# BSPD.net
KiCad netlist of a schematic drawn in Altium Designer
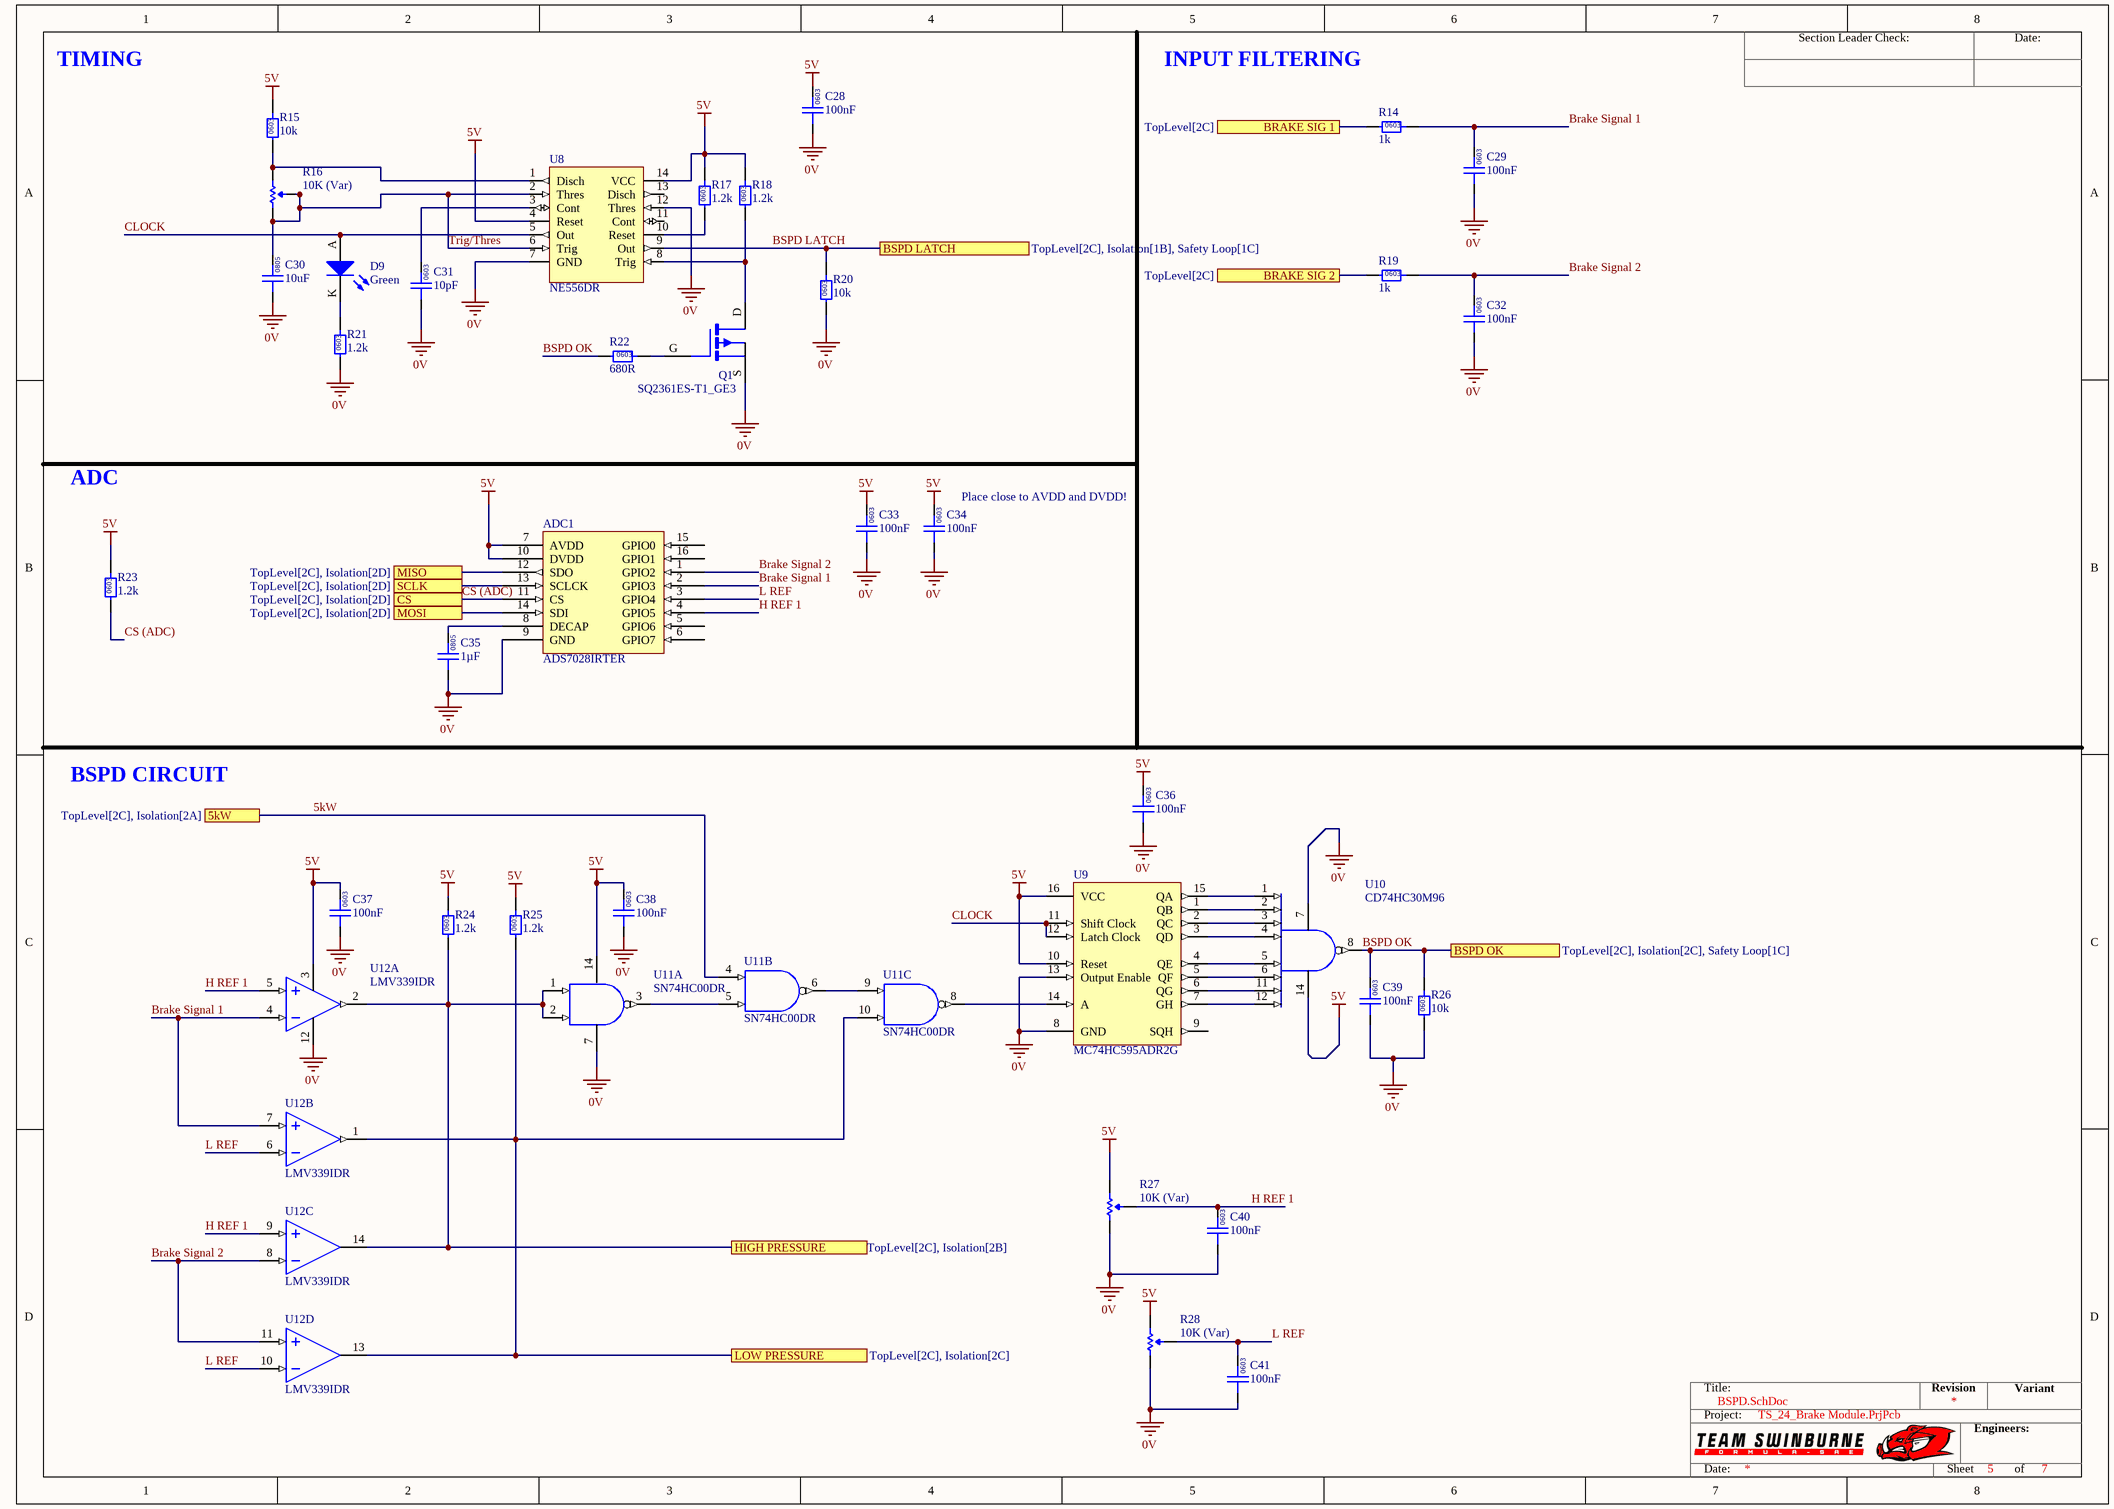
[diagram p0: BSPD.SchDoc]

(export (version "E")
  (design (tool "Eeschema 10.0.6"))
  (components
    (comp (ref "ADC1")
      (value "ADS7028IRTER")
      (footprint "WFQN-16")
      (description "IC ADC 12BIT SAR 16WQFN")
      (fields (field (name "MANUFACTURER") "Texas Instruments"))
      (libsource (lib "ts_standard_library") (part "ADS7028IRTER"))
    )
    (comp (ref "C28")
      (value "100nF")
      (footprint "0603")
      (fields
        (field (name "PART NUMBER") "GCM188L81H104KA57D")
        (field (name "MANUFACTURER") "muRata")
        (field (name "TOLERANCE") "±10%")
      )
      (libsource (lib "ts_standard_library") (part "Capacitor 0603"))
    )
    (comp (ref "C29")
      (value "100nF")
      (footprint "0603")
      (fields
        (field (name "PART NUMBER") "GCM188L81H104KA57D")
        (field (name "MANUFACTURER") "muRata")
        (field (name "TOLERANCE") "±10%")
      )
      (libsource (lib "ts_standard_library") (part "Capacitor 0603"))
    )
    (comp (ref "C30")
      (value "10uF")
      (footprint "0805")
      (fields
        (field (name "PART NUMBER") "GRM21BR6YA106KE43L")
        (field (name "MANUFACTURER") "muRata")
        (field (name "TOLERANCE") "10%")
      )
      (libsource (lib "ts_standard_library") (part "Capacitor 0805"))
    )
    (comp (ref "C31")
      (value "10pF")
      (footprint "0603")
      (fields
        (field (name "PART NUMBER") "GRM1885C1H100JA01D")
        (field (name "MANUFACTURER") "Murata Electronics")
        (field (name "TOLERANCE") "±5%")
      )
      (libsource (lib "ts_standard_library") (part "Capacitor 0603"))
    )
    (comp (ref "C32")
      (value "100nF")
      (footprint "0603")
      (fields
        (field (name "PART NUMBER") "GCM188L81H104KA57D")
        (field (name "MANUFACTURER") "muRata")
        (field (name "TOLERANCE") "±10%")
      )
      (libsource (lib "ts_standard_library") (part "Capacitor 0603"))
    )
    (comp (ref "C33")
      (value "100nF")
      (footprint "0603")
      (fields
        (field (name "PART NUMBER") "GCM188L81H104KA57D")
        (field (name "MANUFACTURER") "muRata")
        (field (name "TOLERANCE") "±10%")
      )
      (libsource (lib "ts_standard_library") (part "Capacitor 0603"))
    )
    (comp (ref "C34")
      (value "100nF")
      (footprint "0603")
      (fields
        (field (name "PART NUMBER") "GCM188L81H104KA57D")
        (field (name "MANUFACTURER") "muRata")
        (field (name "TOLERANCE") "±10%")
      )
      (libsource (lib "ts_standard_library") (part "Capacitor 0603"))
    )
    (comp (ref "C35")
      (value "1µF")
      (footprint "0805")
      (fields
        (field (name "PART NUMBER") "GCM21BR71H105KA03L")
        (field (name "MANUFACTURER") "muRata")
        (field (name "TOLERANCE") "±10%")
      )
      (libsource (lib "ts_standard_library") (part "Capacitor 0805"))
    )
    (comp (ref "C36")
      (value "100nF")
      (footprint "0603")
      (fields
        (field (name "PART NUMBER") "GCM188L81H104KA57D")
        (field (name "MANUFACTURER") "muRata")
        (field (name "TOLERANCE") "±10%")
      )
      (libsource (lib "ts_standard_library") (part "Capacitor 0603"))
    )
    (comp (ref "C37")
      (value "100nF")
      (footprint "0603")
      (fields
        (field (name "PART NUMBER") "GCM188L81H104KA57D")
        (field (name "MANUFACTURER") "muRata")
        (field (name "TOLERANCE") "±10%")
      )
      (libsource (lib "ts_standard_library") (part "Capacitor 0603"))
    )
    (comp (ref "C38")
      (value "100nF")
      (footprint "0603")
      (fields
        (field (name "PART NUMBER") "GCM188L81H104KA57D")
        (field (name "MANUFACTURER") "muRata")
        (field (name "TOLERANCE") "±10%")
      )
      (libsource (lib "ts_standard_library") (part "Capacitor 0603"))
    )
    (comp (ref "C39")
      (value "100nF")
      (footprint "0603")
      (fields
        (field (name "PART NUMBER") "GCM188L81H104KA57D")
        (field (name "MANUFACTURER") "muRata")
        (field (name "TOLERANCE") "±10%")
      )
      (libsource (lib "ts_standard_library") (part "Capacitor 0603"))
    )
    (comp (ref "C40")
      (value "100nF")
      (footprint "0603")
      (fields
        (field (name "PART NUMBER") "GCM188L81H104KA57D")
        (field (name "MANUFACTURER") "muRata")
        (field (name "TOLERANCE") "±10%")
      )
      (libsource (lib "ts_standard_library") (part "Capacitor 0603"))
    )
    (comp (ref "C41")
      (value "100nF")
      (footprint "0603")
      (fields
        (field (name "PART NUMBER") "GCM188L81H104KA57D")
        (field (name "MANUFACTURER") "muRata")
        (field (name "TOLERANCE") "±10%")
      )
      (libsource (lib "ts_standard_library") (part "Capacitor 0603"))
    )
    (comp (ref "D9")
      (value "Green")
      (footprint "0805 LED")
      (description "Green LED Indication - Discrete 1.75V 0805 (2012 Metric)")
      (fields (field (name "PART NUMBER") "SML-210FTT86") (field (name "MANUFACTURER") "ROHM Semiconductor"))
      (libsource (lib "ts_standard_library") (part "LED"))
    )
    (comp (ref "Q1")
      (value "SQ2361ES-T1_GE3")
      (footprint "VSHY SOT-23-3")
      (description "MOSFET P-CH 60V 2.8A SSOT23")
      (fields
        (field (name "MANUFACTURER") "Vishay Siliconix")
        (field (name "DIGIKEY PART NUMBER") "SQ2361ES-T1_GE3CT-ND")
        (field (name "PUBLISHER") "Altium Limited")
      )
      (libsource (lib "ts_standard_library") (part "MOSFET-P"))
    )
    (comp (ref "R14")
      (value "1k")
      (footprint "0603")
      (fields
        (field (name "PART NUMBER") "RC0603FR-071KL")
        (field (name "MANUFACTURER") "YAGEO")
        (field (name "TOLERANCE") "0.01")
      )
      (libsource (lib "ts_standard_library") (part "Resistor 0603"))
    )
    (comp (ref "R15")
      (value "10k")
      (footprint "0603")
      (fields
        (field (name "PART NUMBER") "RC0603FR-0710KL")
        (field (name "MANUFACTURER") "YAGEO")
        (field (name "TOLERANCE") "0.01")
      )
      (libsource (lib "ts_standard_library") (part "Resistor 0603"))
    )
    (comp (ref "R16")
      (value "10K (Var)")
      (footprint "B 3296")
      (fields
        (field (name "PART NUMBER") "3296W-1-103LF")
        (field (name "MANUFACTURER") "Bournes Inc")
        (field (name "TOLERANCE") "0.1")
      )
      (libsource (lib "ts_standard_library") (part "Resistor (Potentiometer)"))
    )
    (comp (ref "R17")
      (value "1.2k")
      (footprint "0603")
      (fields
        (field (name "PART NUMBER") "RC0603JR-071K2L")
        (field (name "MANUFACTURER") "YAGEO")
        (field (name "TOLERANCE") "0.01")
      )
      (libsource (lib "ts_standard_library") (part "Resistor 0603"))
    )
    (comp (ref "R18")
      (value "1.2k")
      (footprint "0603")
      (fields
        (field (name "PART NUMBER") "RC0603JR-071K2L")
        (field (name "MANUFACTURER") "YAGEO")
        (field (name "TOLERANCE") "0.01")
      )
      (libsource (lib "ts_standard_library") (part "Resistor 0603"))
    )
    (comp (ref "R19")
      (value "1k")
      (footprint "0603")
      (fields
        (field (name "PART NUMBER") "RC0603FR-071KL")
        (field (name "MANUFACTURER") "YAGEO")
        (field (name "TOLERANCE") "0.01")
      )
      (libsource (lib "ts_standard_library") (part "Resistor 0603"))
    )
    (comp (ref "R20")
      (value "10k")
      (footprint "0603")
      (fields
        (field (name "PART NUMBER") "RC0603FR-0710KL")
        (field (name "MANUFACTURER") "YAGEO")
        (field (name "TOLERANCE") "0.01")
      )
      (libsource (lib "ts_standard_library") (part "Resistor 0603"))
    )
    (comp (ref "R21")
      (value "1.2k")
      (footprint "0603")
      (fields
        (field (name "PART NUMBER") "RC0603JR-071K2L")
        (field (name "MANUFACTURER") "YAGEO")
        (field (name "TOLERANCE") "0.01")
      )
      (libsource (lib "ts_standard_library") (part "Resistor 0603"))
    )
    (comp (ref "R22")
      (value "680R")
      (footprint "0603")
      (fields
        (field (name "PART NUMBER") "RC0603JR-13680RL")
        (field (name "MANUFACTURER") "YAGEO")
        (field (name "TOLERANCE") "0.01")
      )
      (libsource (lib "ts_standard_library") (part "Resistor 0603"))
    )
    (comp (ref "R23")
      (value "1.2k")
      (footprint "0603")
      (fields
        (field (name "PART NUMBER") "RC0603JR-071K2L")
        (field (name "MANUFACTURER") "YAGEO")
        (field (name "TOLERANCE") "0.01")
      )
      (libsource (lib "ts_standard_library") (part "Resistor 0603"))
    )
    (comp (ref "R24")
      (value "1.2k")
      (footprint "0603")
      (fields
        (field (name "PART NUMBER") "RC0603JR-071K2L")
        (field (name "MANUFACTURER") "YAGEO")
        (field (name "TOLERANCE") "0.01")
      )
      (libsource (lib "ts_standard_library") (part "Resistor 0603"))
    )
    (comp (ref "R25")
      (value "1.2k")
      (footprint "0603")
      (fields
        (field (name "PART NUMBER") "RC0603JR-071K2L")
        (field (name "MANUFACTURER") "YAGEO")
        (field (name "TOLERANCE") "0.01")
      )
      (libsource (lib "ts_standard_library") (part "Resistor 0603"))
    )
    (comp (ref "R26")
      (value "10k")
      (footprint "0603")
      (fields
        (field (name "PART NUMBER") "RC0603FR-0710KL")
        (field (name "MANUFACTURER") "YAGEO")
        (field (name "TOLERANCE") "0.01")
      )
      (libsource (lib "ts_standard_library") (part "Resistor 0603"))
    )
    (comp (ref "R27")
      (value "10K (Var)")
      (footprint "3339P-1-1103LF")
      (fields
        (field (name "PART NUMBER") "3339P-1-1103LF")
        (field (name "MANUFACTURER") "Bournes Inc")
        (field (name "TOLERANCE") "0.1")
      )
      (libsource (lib "ts_standard_library") (part "Resistor (Potentiometer)"))
    )
    (comp (ref "R28")
      (value "10K (Var)")
      (footprint "3339P-1-1103LF")
      (fields
        (field (name "PART NUMBER") "3339P-1-1103LF")
        (field (name "MANUFACTURER") "Bournes Inc")
        (field (name "TOLERANCE") "0.1")
      )
      (libsource (lib "ts_standard_library") (part "Resistor (Potentiometer)"))
    )
    (comp (ref "U8")
      (value "NE556DR")
      (footprint "TI-SOIC14")
      (description "IC OSC TIMER DUAL 100KHZ 14SOIC")
      (fields
        (field (name "MANUFACTURER") "Texas Instruments")
        (field (name "DIGIKEY PART NUMBER") "296-26240-1-ND")
      )
      (libsource (lib "ts_standard_library") (part "NE556DR"))
    )
    (comp (ref "U9")
      (value "MC74HC595ADR2G")
      (footprint "ON 16-SOIC")
      (description "IC SHIFT REGISTR 8BIT 3ST 16SOIC")
      (libsource (lib "Team Swinburne") (part "MC74HC595ADR2G"))
    )
    (comp (ref "U10")
      (value "CD74HC30M96")
      (footprint "TI 14-SOIC")
      (description "IC GATE NAND 1CH 8-INP 14SOIC")
      (libsource (lib "Team Swinburne") (part "CD74HC30M96"))
    )
    (comp (ref "U11")
      (value "SN74HC00DR")
      (footprint "TI 14-SOIC")
      (description "NAND Gate IC 4 Channel 14-SOIC")
      (libsource (lib "Team Swinburne") (part "SN74HC00DR"))
    )
    (comp (ref "U12")
      (value "LMV339IDR")
      (footprint "TI 14-SOIC")
      (description "Comparator General Purpose Open Collector 14-SOIC")
      (libsource (lib "Team Swinburne") (part "LMV339IDR"))
    )
  )
  (nets
    (net (code "1") (name "/5kW") (class "Default")
      (node (ref "U11") (pin "4") (pinfunction "2A_4") (pintype "input"))
    )
    (net (code "2") (name "/BRAKE SIG 1") (class "Default")
      (node (ref "R14") (pin "1") (pinfunction "1_1") (pintype "passive"))
    )
    (net (code "3") (name "/BRAKE SIG 2") (class "Default")
      (node (ref "R19") (pin "1") (pinfunction "1_1") (pintype "passive"))
    )
    (net (code "4") (name "/BSPD LATCH") (class "Default")
      (node (ref "R20") (pin "2") (pinfunction "2_2") (pintype "passive"))
      (node (ref "U8") (pin "9") (pinfunction "Out_9") (pintype "output"))
    )
    (net (code "5") (name "/BSPD OK") (class "Default")
      (node (ref "C39") (pin "2") (pinfunction "2_2") (pintype "passive"))
      (node (ref "R22") (pin "1") (pinfunction "1_1") (pintype "passive"))
      (node (ref "R26") (pin "2") (pinfunction "2_2") (pintype "passive"))
      (node (ref "U10") (pin "8") (pinfunction "Output_8") (pintype "output"))
    )
    (net (code "6") (name "/Brake Signal 1") (class "Default")
      (node (ref "ADC1") (pin "2") (pinfunction "GPIO3_2") (pintype "input"))
      (node (ref "C29") (pin "2") (pinfunction "2_2") (pintype "passive"))
      (node (ref "R14") (pin "2") (pinfunction "2_2") (pintype "passive"))
      (node (ref "U12") (pin "4") (pinfunction "IN_A-_4") (pintype "input"))
      (node (ref "U12") (pin "7") (pinfunction "IN_B+_7") (pintype "input"))
    )
    (net (code "7") (name "/Brake Signal 2") (class "Default")
      (node (ref "ADC1") (pin "1") (pinfunction "GPIO2_1") (pintype "input"))
      (node (ref "C32") (pin "2") (pinfunction "2_2") (pintype "passive"))
      (node (ref "R19") (pin "2") (pinfunction "2_2") (pintype "passive"))
      (node (ref "U12") (pin "11") (pinfunction "IN_D+_11") (pintype "input"))
      (node (ref "U12") (pin "8") (pinfunction "IN_C-_8") (pintype "input"))
    )
    (net (code "8") (name "/CLOCK") (class "Default")
      (node (ref "D9") (pin "A") (pinfunction "A_A") (pintype "passive"))
      (node (ref "U8") (pin "5") (pinfunction "Out_5") (pintype "output"))
      (node (ref "U9") (pin "11") (pinfunction "Shift_Clock_11") (pintype "input"))
      (node (ref "U9") (pin "12") (pinfunction "Latch_Clock_12") (pintype "input"))
    )
    (net (code "9") (name "/CS (ADC)") (class "Default")
      (node (ref "ADC1") (pin "11") (pinfunction "CS_11") (pintype "input"))
      (node (ref "R23") (pin "1") (pinfunction "1_1") (pintype "passive"))
    )
    (net (code "10") (name "/H REF 1") (class "Default")
      (node (ref "ADC1") (pin "4") (pinfunction "GPIO5_4") (pintype "input"))
      (node (ref "C40") (pin "2") (pinfunction "2_2") (pintype "passive"))
      (node (ref "R27") (pin "2") (pinfunction "Wiper_2") (pintype "passive"))
      (node (ref "U12") (pin "5") (pinfunction "IN_A+_5") (pintype "input"))
      (node (ref "U12") (pin "9") (pinfunction "IN_C+_9") (pintype "input"))
    )
    (net (code "11") (name "/HIGH PRESSURE") (class "Default")
      (node (ref "R24") (pin "1") (pinfunction "1_1") (pintype "passive"))
      (node (ref "U11") (pin "1") (pinfunction "1A_1") (pintype "input"))
      (node (ref "U11") (pin "2") (pinfunction "1B_2") (pintype "input"))
      (node (ref "U12") (pin "14") (pinfunction "OUT_C_14") (pintype "passive"))
      (node (ref "U12") (pin "2") (pinfunction "OUT_A_2") (pintype "output"))
    )
    (net (code "12") (name "/L REF") (class "Default")
      (node (ref "ADC1") (pin "3") (pinfunction "GPIO4_3") (pintype "input"))
      (node (ref "C41") (pin "2") (pinfunction "2_2") (pintype "passive"))
      (node (ref "R28") (pin "2") (pinfunction "Wiper_2") (pintype "passive"))
      (node (ref "U12") (pin "10") (pinfunction "IN_D-_10") (pintype "input"))
      (node (ref "U12") (pin "6") (pinfunction "IN_B-_6") (pintype "input"))
    )
    (net (code "13") (name "/LOW PRESSURE") (class "Default")
      (node (ref "R25") (pin "1") (pinfunction "1_1") (pintype "passive"))
      (node (ref "U11") (pin "10") (pinfunction "3B_10") (pintype "input"))
      (node (ref "U12") (pin "1") (pinfunction "OUT_B_1") (pintype "output"))
      (node (ref "U12") (pin "13") (pinfunction "OUT_D_13") (pintype "passive"))
    )
    (net (code "14") (name "/MISO") (class "Default")
      (node (ref "ADC1") (pin "12") (pinfunction "SDO_12") (pintype "output"))
    )
    (net (code "15") (name "/MOSI") (class "Default")
      (node (ref "ADC1") (pin "14") (pinfunction "SDI_14") (pintype "input"))
    )
    (net (code "16") (name "/SCLK") (class "Default")
      (node (ref "ADC1") (pin "13") (pinfunction "SCLCK_13") (pintype "input"))
    )
    (net (code "17") (name "/Trig{slash}Thres") (class "Default")
      (node (ref "C30") (pin "2") (pinfunction "2_2") (pintype "passive"))
      (node (ref "R16") (pin "2") (pinfunction "Wiper_2") (pintype "passive"))
      (node (ref "R16") (pin "3") (pinfunction "CW_3") (pintype "passive"))
      (node (ref "U8") (pin "2") (pinfunction "Thres_2") (pintype "input"))
      (node (ref "U8") (pin "6") (pinfunction "Trig_6") (pintype "input"))
    )
    (net (code "18") (name "0V") (class "Default")
      (node (ref "ADC1") (pin "9") (pinfunction "GND_9") (pintype "power_in"))
      (node (ref "C28") (pin "1") (pinfunction "1_1") (pintype "passive"))
      (node (ref "C29") (pin "1") (pinfunction "1_1") (pintype "passive"))
      (node (ref "C30") (pin "1") (pinfunction "1_1") (pintype "passive"))
      (node (ref "C31") (pin "1") (pinfunction "1_1") (pintype "passive"))
      (node (ref "C32") (pin "1") (pinfunction "1_1") (pintype "passive"))
      (node (ref "C33") (pin "1") (pinfunction "1_1") (pintype "passive"))
      (node (ref "C34") (pin "1") (pinfunction "1_1") (pintype "passive"))
      (node (ref "C35") (pin "1") (pinfunction "1_1") (pintype "passive"))
      (node (ref "C36") (pin "1") (pinfunction "1_1") (pintype "passive"))
      (node (ref "C37") (pin "1") (pinfunction "1_1") (pintype "passive"))
      (node (ref "C38") (pin "1") (pinfunction "1_1") (pintype "passive"))
      (node (ref "C39") (pin "1") (pinfunction "1_1") (pintype "passive"))
      (node (ref "C40") (pin "1") (pinfunction "1_1") (pintype "passive"))
      (node (ref "C41") (pin "1") (pinfunction "1_1") (pintype "passive"))
      (node (ref "Q1") (pin "S") (pinfunction "S_S") (pintype "passive"))
      (node (ref "R20") (pin "1") (pinfunction "1_1") (pintype "passive"))
      (node (ref "R21") (pin "1") (pinfunction "1_1") (pintype "passive"))
      (node (ref "R26") (pin "1") (pinfunction "1_1") (pintype "passive"))
      (node (ref "R27") (pin "3") (pinfunction "CW_3") (pintype "passive"))
      (node (ref "R28") (pin "3") (pinfunction "CW_3") (pintype "passive"))
      (node (ref "U10") (pin "7") (pinfunction "GND_7") (pintype "power_in"))
      (node (ref "U11") (pin "7") (pinfunction "GND_7") (pintype "power_in"))
      (node (ref "U12") (pin "12") (pinfunction "V-_12") (pintype "power_in"))
      (node (ref "U8") (pin "12") (pinfunction "Thres_12") (pintype "input"))
      (node (ref "U8") (pin "7") (pinfunction "GND_7") (pintype "power_in"))
      (node (ref "U9") (pin "13") (pinfunction "Output_Enable_13") (pintype "input"))
      (node (ref "U9") (pin "8") (pinfunction "GND_8") (pintype "power_in"))
    )
    (net (code "19") (name "5V") (class "Default")
      (node (ref "ADC1") (pin "10") (pinfunction "DVDD_10") (pintype "power_in"))
      (node (ref "ADC1") (pin "7") (pinfunction "AVDD_7") (pintype "power_in"))
      (node (ref "C28") (pin "2") (pinfunction "2_2") (pintype "passive"))
      (node (ref "C33") (pin "2") (pinfunction "2_2") (pintype "passive"))
      (node (ref "C34") (pin "2") (pinfunction "2_2") (pintype "passive"))
      (node (ref "C36") (pin "2") (pinfunction "2_2") (pintype "passive"))
      (node (ref "C37") (pin "2") (pinfunction "2_2") (pintype "passive"))
      (node (ref "C38") (pin "2") (pinfunction "2_2") (pintype "passive"))
      (node (ref "R15") (pin "2") (pinfunction "2_2") (pintype "passive"))
      (node (ref "R17") (pin "2") (pinfunction "2_2") (pintype "passive"))
      (node (ref "R18") (pin "2") (pinfunction "2_2") (pintype "passive"))
      (node (ref "R23") (pin "2") (pinfunction "2_2") (pintype "passive"))
      (node (ref "R24") (pin "2") (pinfunction "2_2") (pintype "passive"))
      (node (ref "R25") (pin "2") (pinfunction "2_2") (pintype "passive"))
      (node (ref "R27") (pin "1") (pinfunction "CCW_1") (pintype "passive"))
      (node (ref "R28") (pin "1") (pinfunction "CCW_1") (pintype "passive"))
      (node (ref "U10") (pin "14") (pinfunction "VCC_14") (pintype "power_in"))
      (node (ref "U11") (pin "14") (pinfunction "VCC_14") (pintype "power_in"))
      (node (ref "U12") (pin "3") (pinfunction "V+_3") (pintype "power_in"))
      (node (ref "U8") (pin "14") (pinfunction "VCC_14") (pintype "passive"))
      (node (ref "U8") (pin "4") (pinfunction "Reset_4") (pintype "passive"))
      (node (ref "U9") (pin "10") (pinfunction "Reset_10") (pintype "input"))
      (node (ref "U9") (pin "16") (pinfunction "VCC_16") (pintype "power_in"))
    )
    (net (code "20") (name "Net-(ADC1-DECAP)") (class "Default")
      (node (ref "ADC1") (pin "8") (pinfunction "DECAP_8") (pintype "power_in"))
      (node (ref "C35") (pin "2") (pinfunction "2_2") (pintype "passive"))
    )
    (net (code "21") (name "Net-(C31-Pad2)") (class "Default")
      (node (ref "C31") (pin "2") (pinfunction "2_2") (pintype "passive"))
      (node (ref "U8") (pin "3") (pinfunction "Cont_3") (pintype "bidirectional"))
    )
    (net (code "22") (name "Net-(D9-PadK)") (class "Default")
      (node (ref "D9") (pin "K") (pinfunction "K_K") (pintype "passive"))
      (node (ref "R21") (pin "2") (pinfunction "2_2") (pintype "passive"))
    )
    (net (code "23") (name "Net-(Q1-PadD)") (class "Default")
      (node (ref "Q1") (pin "D") (pinfunction "D_D") (pintype "passive"))
      (node (ref "R18") (pin "1") (pinfunction "1_1") (pintype "passive"))
      (node (ref "U8") (pin "8") (pinfunction "Trig_8") (pintype "input"))
    )
    (net (code "24") (name "Net-(Q1-PadG)") (class "Default")
      (node (ref "Q1") (pin "G") (pinfunction "G_G") (pintype "passive"))
      (node (ref "R22") (pin "2") (pinfunction "2_2") (pintype "passive"))
    )
    (net (code "25") (name "Net-(R16-CCW)") (class "Default")
      (node (ref "R15") (pin "1") (pinfunction "1_1") (pintype "passive"))
      (node (ref "R16") (pin "1") (pinfunction "CCW_1") (pintype "passive"))
      (node (ref "U8") (pin "1") (pinfunction "Disch_1") (pintype "output"))
    )
    (net (code "26") (name "Net-(R17-Pad1)") (class "Default")
      (node (ref "R17") (pin "1") (pinfunction "1_1") (pintype "passive"))
      (node (ref "U8") (pin "10") (pinfunction "Reset_10") (pintype "passive"))
    )
    (net (code "27") (name "Net-(U9-GH)") (class "Default")
      (node (ref "U10") (pin "12") (pinfunction "Input_12") (pintype "input"))
      (node (ref "U9") (pin "7") (pinfunction "GH_7") (pintype "output"))
    )
    (net (code "28") (name "Net-(U9-QA)") (class "Default")
      (node (ref "U10") (pin "1") (pinfunction "Input_1") (pintype "input"))
      (node (ref "U9") (pin "15") (pinfunction "QA_15") (pintype "output"))
    )
    (net (code "29") (name "Net-(U9-QB)") (class "Default")
      (node (ref "U10") (pin "2") (pinfunction "Input_2") (pintype "input"))
      (node (ref "U9") (pin "1") (pinfunction "QB_1") (pintype "output"))
    )
    (net (code "30") (name "Net-(U9-QC)") (class "Default")
      (node (ref "U10") (pin "3") (pinfunction "Input_3") (pintype "input"))
      (node (ref "U9") (pin "2") (pinfunction "QC_2") (pintype "output"))
    )
    (net (code "31") (name "Net-(U9-QD)") (class "Default")
      (node (ref "U10") (pin "4") (pinfunction "Input_4") (pintype "input"))
      (node (ref "U9") (pin "3") (pinfunction "QD_3") (pintype "output"))
    )
    (net (code "32") (name "Net-(U9-QE)") (class "Default")
      (node (ref "U10") (pin "5") (pinfunction "Input_5") (pintype "input"))
      (node (ref "U9") (pin "4") (pinfunction "QE_4") (pintype "output"))
    )
    (net (code "33") (name "Net-(U9-QF)") (class "Default")
      (node (ref "U10") (pin "6") (pinfunction "Input_6") (pintype "input"))
      (node (ref "U9") (pin "5") (pinfunction "QF_5") (pintype "output"))
    )
    (net (code "34") (name "Net-(U9-QG)") (class "Default")
      (node (ref "U10") (pin "11") (pinfunction "Input_11") (pintype "input"))
      (node (ref "U9") (pin "6") (pinfunction "QG_6") (pintype "output"))
    )
    (net (code "35") (name "Net-(U11A-1Y)") (class "Default")
      (node (ref "U11") (pin "3") (pinfunction "1Y_3") (pintype "output"))
      (node (ref "U11") (pin "5") (pinfunction "2B_5") (pintype "input"))
    )
    (net (code "36") (name "Net-(U11B-2Y)") (class "Default")
      (node (ref "U11") (pin "6") (pinfunction "2Y_6") (pintype "output"))
      (node (ref "U11") (pin "9") (pinfunction "3A_9") (pintype "input"))
    )
    (net (code "37") (name "Net-(U11C-3Y)") (class "Default")
      (node (ref "U11") (pin "8") (pinfunction "3Y_8") (pintype "output"))
      (node (ref "U9") (pin "14") (pinfunction "A_14") (pintype "input"))
    )
    (net (code "38") (name "unconnected-(ADC1-GPIO0-Pad15)") (class "Default")
      (node (ref "ADC1") (pin "15") (pinfunction "GPIO0_15") (pintype "input"))
    )
    (net (code "39") (name "unconnected-(ADC1-GPIO1-Pad16)") (class "Default")
      (node (ref "ADC1") (pin "16") (pinfunction "GPIO1_16") (pintype "input"))
    )
    (net (code "40") (name "unconnected-(ADC1-GPIO6-Pad5)") (class "Default")
      (node (ref "ADC1") (pin "5") (pinfunction "GPIO6_5") (pintype "input"))
    )
    (net (code "41") (name "unconnected-(ADC1-GPIO7-Pad6)") (class "Default")
      (node (ref "ADC1") (pin "6") (pinfunction "GPIO7_6") (pintype "input"))
    )
    (net (code "42") (name "unconnected-(U8-Cont-Pad11)") (class "Default")
      (node (ref "U8") (pin "11") (pinfunction "Cont_11") (pintype "bidirectional"))
    )
    (net (code "43") (name "unconnected-(U8-Disch-Pad13)") (class "Default")
      (node (ref "U8") (pin "13") (pinfunction "Disch_13") (pintype "output"))
    )
    (net (code "44") (name "unconnected-(U9-SQH-Pad9)") (class "Default")
      (node (ref "U9") (pin "9") (pinfunction "SQH_9") (pintype "output"))
    )
  )
)
